# SipNPuff.net
KiCad netlist of a schematic drawn in EAGLE
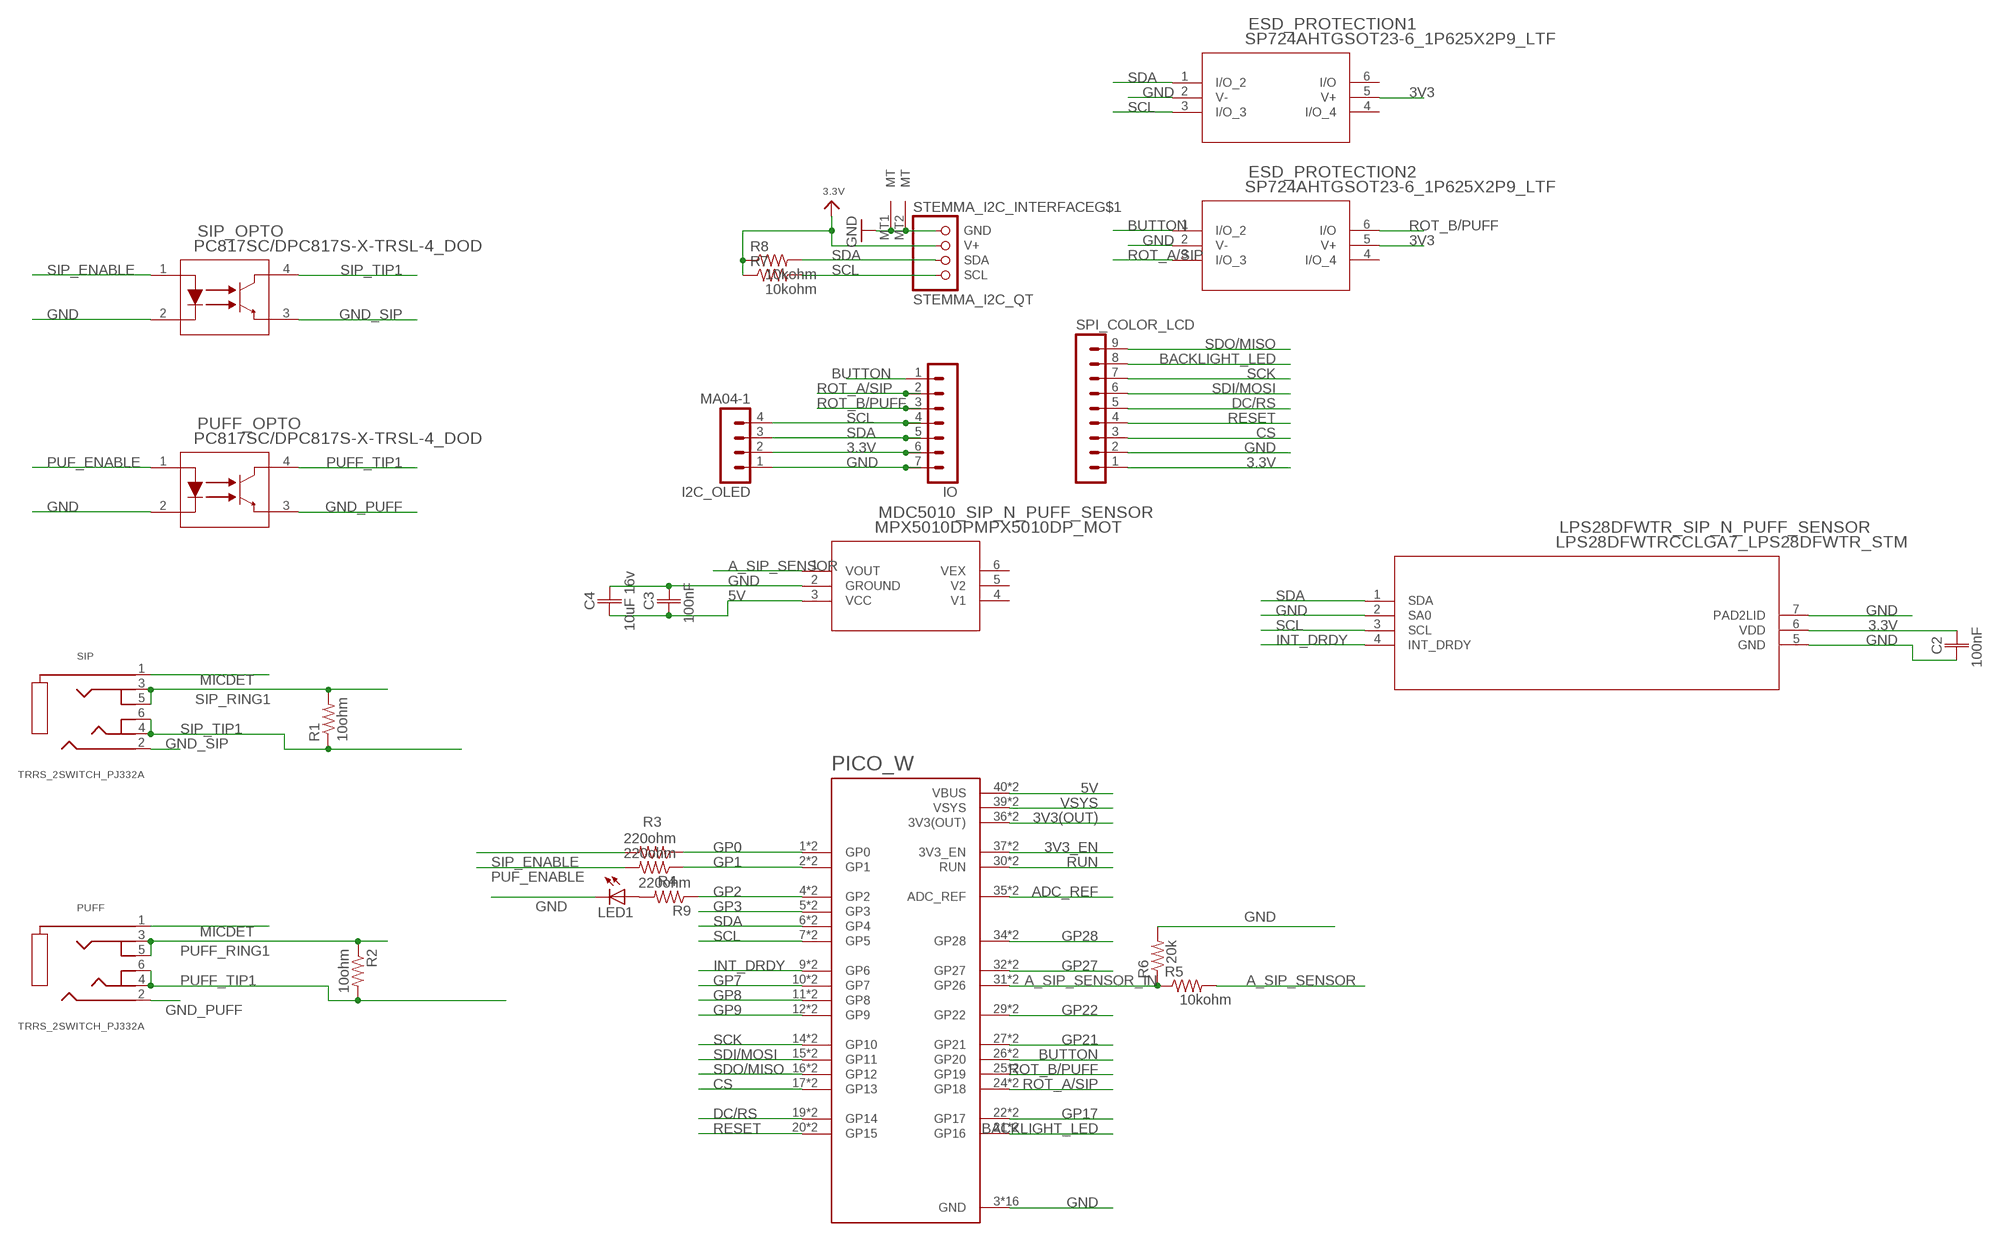
[diagram p0: schematic, sheet 1]

(export (version "E")
  (design (tool "Eeschema 10.0.6"))
  (components
    (comp (ref "C2")
      (value "100nF")
      (footprint "eagle-import:CAPC2012X110")
      (libsource (lib "eagle-import") (part "CCHIP-0805(2012-METRIC)_"))
    )
    (comp (ref "C3")
      (value "100nF")
      (footprint "eagle-import:CAPC2012X110")
      (libsource (lib "eagle-import") (part "CCHIP-0805(2012-METRIC)_"))
    )
    (comp (ref "C4")
      (value "10uF 16v")
      (footprint "eagle-import:CAPC2012X110")
      (libsource (lib "eagle-import") (part "CCHIP-0805(2012-METRIC)_"))
    )
    (comp (ref "ESD_PROTECTION1")
      (value "SP724AHTGSOT23-6_1P625X2P9_LTF")
      (footprint "eagle-import:SOT23-6_1P625X2P9_LTF")
      (fields
        (field (name "MANUFACTURER_PART_NUMBER") "SP724AHTG")
        (field (name "COPYRIGHT") "Copyright (C) 2022 Ultra Librarian. All rights reserved.")
      )
      (libsource (lib "eagle-import") (part "SP724AHTGSOT23-6_1P625X2P9_LTF"))
    )
    (comp (ref "ESD_PROTECTION2")
      (value "SP724AHTGSOT23-6_1P625X2P9_LTF")
      (footprint "eagle-import:SOT23-6_1P625X2P9_LTF")
      (fields
        (field (name "MANUFACTURER_PART_NUMBER") "SP724AHTG")
        (field (name "COPYRIGHT") "Copyright (C) 2022 Ultra Librarian. All rights reserved.")
      )
      (libsource (lib "eagle-import") (part "SP724AHTGSOT23-6_1P625X2P9_LTF"))
    )
    (comp (ref "I2C_OLED")
      (value "MA04-1")
      (footprint "eagle-import:MA04-1")
      (libsource (lib "eagle-import") (part "MA04-1"))
    )
    (comp (ref "IO")
      (value "MA07-1")
      (footprint "eagle-import:MA07-1")
      (libsource (lib "eagle-import") (part "MA07-1"))
    )
    (comp (ref "LED1")
      (value "LEDCHIP-LED0805")
      (footprint "eagle-import:CHIP-LED0805")
      (libsource (lib "eagle-import") (part "LEDCHIP-LED0805"))
    )
    (comp (ref "LPS28DFWTR_SIP_N_PUFF_SENSOR")
      (value "LPS28DFWTRCCLGA7_LPS28DFWTR_STM")
      (footprint "eagle-import:CCLGA7_LPS28DFWTR_STM")
      (fields
        (field (name "MANUFACTURER_PART_NUMBER") "LPS28DFWTR")
        (field (name "COPYRIGHT") "Copyright (C) 2026 Ultra Librarian. All rights reserved.")
      )
      (libsource (lib "eagle-import") (part "LPS28DFWTRCCLGA7_LPS28DFWTR_STM"))
    )
    (comp (ref "MDC5010_SIP_N_PUFF_SENSOR")
      (value "MPX5010DPMPX5010DP_MOT")
      (footprint "eagle-import:MPX5010DP_MOT")
      (fields
        (field (name "MANUFACTURER_PART_NUMBER") "MPX5010DP")
        (field (name "COPYRIGHT") "Copyright (C) 2026 Ultra Librarian. All rights reserved.")
      )
      (libsource (lib "eagle-import") (part "MPX5010DPMPX5010DP_MOT"))
    )
    (comp (ref "PICO_W")
      (value "RASPBERRY_PICO-NO_DEBUG")
      (footprint "eagle-import:PICO-PKG-NO_DEBUG")
      (libsource (lib "eagle-import") (part "RASPBERRY_PICO-NO_DEBUG"))
    )
    (comp (ref "PUFF")
      (value "TRRS_2SWITCH_PJ332A")
      (footprint "eagle-import:PJ-332A")
      (libsource (lib "eagle-import") (part "TRRS_2SWITCH_PJ332A"))
    )
    (comp (ref "PUFF_OPTO")
      (value "PC817SC/DPC817S-X-TRSL-4_DOD")
      (footprint "eagle-import:SL-4_DOD")
      (fields
        (field (name "MANUFACTURER_PART_NUMBER") "DPC817S-X-TR")
        (field (name "COPYRIGHT") "Copyright (C) 2026 Ultra Librarian. All rights reserved.")
      )
      (libsource (lib "eagle-import") (part "DPC817S-X-TRSL-4_DOD"))
    )
    (comp (ref "R1")
      (value "10ohm")
      (footprint "eagle-import:R0805")
      (libsource (lib "eagle-import") (part "R-US_R0805"))
    )
    (comp (ref "R2")
      (value "10ohm")
      (footprint "eagle-import:R0805")
      (libsource (lib "eagle-import") (part "R-US_R0805"))
    )
    (comp (ref "R3")
      (value "220ohm")
      (footprint "eagle-import:R0805")
      (libsource (lib "eagle-import") (part "R-US_R0805"))
    )
    (comp (ref "R4")
      (value "220ohm")
      (footprint "eagle-import:R0805")
      (libsource (lib "eagle-import") (part "R-US_R0805"))
    )
    (comp (ref "R5")
      (value "10kohm")
      (footprint "eagle-import:R0805")
      (libsource (lib "eagle-import") (part "R-US_R0805"))
    )
    (comp (ref "R6")
      (value "20k")
      (footprint "eagle-import:R0805")
      (libsource (lib "eagle-import") (part "R-US_R0805"))
    )
    (comp (ref "R7")
      (value "10kohm")
      (footprint "eagle-import:R0805")
      (libsource (lib "eagle-import") (part "R-US_R0805"))
    )
    (comp (ref "R8")
      (value "10kohm")
      (footprint "eagle-import:R0805")
      (libsource (lib "eagle-import") (part "R-US_R0805"))
    )
    (comp (ref "R9")
      (value "220ohm")
      (footprint "eagle-import:R0805")
      (libsource (lib "eagle-import") (part "R-US_R0805"))
    )
    (comp (ref "SIP")
      (value "TRRS_2SWITCH_PJ332A")
      (footprint "eagle-import:PJ-332A")
      (libsource (lib "eagle-import") (part "TRRS_2SWITCH_PJ332A"))
    )
    (comp (ref "SIP_OPTO")
      (value "PC817SC/DPC817S-X-TRSL-4_DOD")
      (footprint "eagle-import:SL-4_DOD")
      (fields
        (field (name "MANUFACTURER_PART_NUMBER") "DPC817S-X-TR")
        (field (name "COPYRIGHT") "Copyright (C) 2026 Ultra Librarian. All rights reserved.")
      )
      (libsource (lib "eagle-import") (part "DPC817S-X-TRSL-4_DOD"))
    )
    (comp (ref "SPI_COLOR_LCD")
      (value "MA09-1")
      (footprint "eagle-import:MA09-1")
      (libsource (lib "eagle-import") (part "MA09-1"))
    )
    (comp (ref "STEMMA_I2C_INTERFACE")
      (value "STEMMA_I2C_QT")
      (footprint "eagle-import:JST_SH4")
      (libsource (lib "eagle-import") (part "STEMMA_I2C_QT"))
    )
  )
  (nets
    (net (code "1") (name "/3V3") (class "Default")
      (node (ref "ESD_PROTECTION1") (pin "5") (pinfunction "V+_5") (pintype "power_in"))
      (node (ref "ESD_PROTECTION2") (pin "5") (pinfunction "V+_5") (pintype "power_in"))
    )
    (net (code "2") (name "/3V3(OUT)") (class "Default")
      (node (ref "PICO_W") (pin "36") (pinfunction "3V3(OUT)_36") (pintype "power_in"))
      (node (ref "PICO_W") (pin "P$36") (pinfunction "3V3(OUT)_P$36") (pintype "power_in"))
    )
    (net (code "3") (name "/3V3_EN") (class "Default")
      (node (ref "PICO_W") (pin "37") (pinfunction "3V3_EN_37") (pintype "input"))
      (node (ref "PICO_W") (pin "P$37") (pinfunction "3V3_EN_P$37") (pintype "input"))
    )
    (net (code "4") (name "/5V") (class "Default")
      (node (ref "C3") (pin "1") (pinfunction "1_1") (pintype "passive"))
      (node (ref "C4") (pin "1") (pinfunction "1_1") (pintype "passive"))
      (node (ref "MDC5010_SIP_N_PUFF_SENSOR") (pin "3") (pinfunction "VCC_3") (pintype "power_in"))
      (node (ref "PICO_W") (pin "40") (pinfunction "VBUS_40") (pintype "power_in"))
      (node (ref "PICO_W") (pin "P$40") (pinfunction "VBUS_P$40") (pintype "power_in"))
    )
    (net (code "5") (name "/ADC_REF") (class "Default")
      (node (ref "PICO_W") (pin "35") (pinfunction "ADC_REF_35") (pintype "input"))
      (node (ref "PICO_W") (pin "P$35") (pinfunction "ADC_REF_P$35") (pintype "input"))
    )
    (net (code "6") (name "/A_SIP_SENSOR") (class "Default")
      (node (ref "MDC5010_SIP_N_PUFF_SENSOR") (pin "1") (pinfunction "VOUT_1") (pintype "output"))
      (node (ref "R5") (pin "2") (pinfunction "2_2") (pintype "passive"))
    )
    (net (code "7") (name "/A_SIP_SENSOR_IN") (class "Default")
      (node (ref "PICO_W") (pin "31") (pinfunction "GP26_31") (pintype "bidirectional"))
      (node (ref "PICO_W") (pin "P$31") (pinfunction "GP26_P$31") (pintype "bidirectional"))
      (node (ref "R5") (pin "1") (pinfunction "1_1") (pintype "passive"))
      (node (ref "R6") (pin "1") (pinfunction "1_1") (pintype "passive"))
    )
    (net (code "8") (name "/BACKLIGHT_LED") (class "Default")
      (node (ref "PICO_W") (pin "21") (pinfunction "GP16_21") (pintype "bidirectional"))
      (node (ref "PICO_W") (pin "P$21") (pinfunction "GP16_P$21") (pintype "bidirectional"))
      (node (ref "SPI_COLOR_LCD") (pin "8") (pinfunction "8_8") (pintype "passive"))
    )
    (net (code "9") (name "/BUTTON") (class "Default")
      (node (ref "ESD_PROTECTION2") (pin "1") (pinfunction "I/O_2_1") (pintype "passive"))
      (node (ref "IO") (pin "1") (pinfunction "1_1") (pintype "passive"))
      (node (ref "PICO_W") (pin "26") (pinfunction "GP20_26") (pintype "bidirectional"))
      (node (ref "PICO_W") (pin "P$26") (pinfunction "GP20_P$26") (pintype "bidirectional"))
    )
    (net (code "10") (name "/CS") (class "Default")
      (node (ref "PICO_W") (pin "17") (pinfunction "GP13_17") (pintype "bidirectional"))
      (node (ref "PICO_W") (pin "P$17") (pinfunction "GP13_P$17") (pintype "bidirectional"))
      (node (ref "SPI_COLOR_LCD") (pin "3") (pinfunction "3_3") (pintype "passive"))
    )
    (net (code "11") (name "/DC{slash}RS") (class "Default")
      (node (ref "PICO_W") (pin "19") (pinfunction "GP14_19") (pintype "bidirectional"))
      (node (ref "PICO_W") (pin "P$19") (pinfunction "GP14_P$19") (pintype "bidirectional"))
      (node (ref "SPI_COLOR_LCD") (pin "5") (pinfunction "5_5") (pintype "passive"))
    )
    (net (code "12") (name "/GND_PUFF") (class "Default")
      (node (ref "PUFF") (pin "2") (pinfunction "RING1_2") (pintype "passive"))
      (node (ref "PUFF_OPTO") (pin "3") (pinfunction "EMITTER_3") (pintype "passive"))
    )
    (net (code "13") (name "/GND_SIP") (class "Default")
      (node (ref "SIP") (pin "2") (pinfunction "RING1_2") (pintype "passive"))
      (node (ref "SIP_OPTO") (pin "3") (pinfunction "EMITTER_3") (pintype "passive"))
    )
    (net (code "14") (name "/GP0") (class "Default")
      (node (ref "PICO_W") (pin "1") (pinfunction "GP0_1") (pintype "bidirectional"))
      (node (ref "PICO_W") (pin "P$1") (pinfunction "GP0_P$1") (pintype "bidirectional"))
      (node (ref "R3") (pin "1") (pinfunction "1_1") (pintype "passive"))
    )
    (net (code "15") (name "/GP1") (class "Default")
      (node (ref "PICO_W") (pin "2") (pinfunction "GP1_2") (pintype "bidirectional"))
      (node (ref "PICO_W") (pin "P$2") (pinfunction "GP1_P$2") (pintype "bidirectional"))
      (node (ref "R4") (pin "1") (pinfunction "1_1") (pintype "passive"))
    )
    (net (code "16") (name "/GP2") (class "Default")
      (node (ref "PICO_W") (pin "4") (pinfunction "GP2_4") (pintype "bidirectional"))
      (node (ref "PICO_W") (pin "P$4") (pinfunction "GP2_P$4") (pintype "bidirectional"))
      (node (ref "R9") (pin "1") (pinfunction "1_1") (pintype "passive"))
    )
    (net (code "17") (name "/GP3") (class "Default")
      (node (ref "PICO_W") (pin "5") (pinfunction "GP3_5") (pintype "bidirectional"))
      (node (ref "PICO_W") (pin "P$5") (pinfunction "GP3_P$5") (pintype "bidirectional"))
    )
    (net (code "18") (name "/GP7") (class "Default")
      (node (ref "PICO_W") (pin "10") (pinfunction "GP7_10") (pintype "bidirectional"))
      (node (ref "PICO_W") (pin "P$10") (pinfunction "GP7_P$10") (pintype "bidirectional"))
    )
    (net (code "19") (name "/GP8") (class "Default")
      (node (ref "PICO_W") (pin "11") (pinfunction "GP8_11") (pintype "bidirectional"))
      (node (ref "PICO_W") (pin "P$11") (pinfunction "GP8_P$11") (pintype "bidirectional"))
    )
    (net (code "20") (name "/GP9") (class "Default")
      (node (ref "PICO_W") (pin "12") (pinfunction "GP9_12") (pintype "bidirectional"))
      (node (ref "PICO_W") (pin "P$12") (pinfunction "GP9_P$12") (pintype "bidirectional"))
    )
    (net (code "21") (name "/GP17") (class "Default")
      (node (ref "PICO_W") (pin "22") (pinfunction "GP17_22") (pintype "bidirectional"))
      (node (ref "PICO_W") (pin "P$22") (pinfunction "GP17_P$22") (pintype "bidirectional"))
    )
    (net (code "22") (name "/GP21") (class "Default")
      (node (ref "PICO_W") (pin "27") (pinfunction "GP21_27") (pintype "bidirectional"))
      (node (ref "PICO_W") (pin "P$27") (pinfunction "GP21_P$27") (pintype "bidirectional"))
    )
    (net (code "23") (name "/GP22") (class "Default")
      (node (ref "PICO_W") (pin "29") (pinfunction "GP22_29") (pintype "bidirectional"))
      (node (ref "PICO_W") (pin "P$29") (pinfunction "GP22_P$29") (pintype "bidirectional"))
    )
    (net (code "24") (name "/GP27") (class "Default")
      (node (ref "PICO_W") (pin "32") (pinfunction "GP27_32") (pintype "bidirectional"))
      (node (ref "PICO_W") (pin "P$32") (pinfunction "GP27_P$32") (pintype "bidirectional"))
    )
    (net (code "25") (name "/GP28") (class "Default")
      (node (ref "PICO_W") (pin "34") (pinfunction "GP28_34") (pintype "bidirectional"))
      (node (ref "PICO_W") (pin "P$34") (pinfunction "GP28_P$34") (pintype "bidirectional"))
    )
    (net (code "26") (name "/INT_DRDY") (class "Default")
      (node (ref "LPS28DFWTR_SIP_N_PUFF_SENSOR") (pin "4") (pinfunction "INT_DRDY_4") (pintype "input"))
      (node (ref "PICO_W") (pin "9") (pinfunction "GP6_9") (pintype "bidirectional"))
      (node (ref "PICO_W") (pin "P$9") (pinfunction "GP6_P$9") (pintype "bidirectional"))
    )
    (net (code "27") (name "/MICDET") (class "Default")
      (node (ref "PUFF") (pin "1") (pinfunction "RING_1") (pintype "passive"))
      (node (ref "SIP") (pin "1") (pinfunction "RING_1") (pintype "passive"))
    )
    (net (code "28") (name "/PUFF_RING1") (class "Default")
      (node (ref "PUFF") (pin "3") (pinfunction "RING2_3") (pintype "passive"))
      (node (ref "PUFF") (pin "5") (pinfunction "R2_SW_5") (pintype "passive"))
      (node (ref "R2") (pin "1") (pinfunction "1_1") (pintype "passive"))
    )
    (net (code "29") (name "/PUFF_TIP1") (class "Default")
      (node (ref "PUFF") (pin "4") (pinfunction "TIP_4") (pintype "passive"))
      (node (ref "PUFF") (pin "6") (pinfunction "TIP_SW_6") (pintype "passive"))
      (node (ref "PUFF_OPTO") (pin "4") (pinfunction "COLLECTOR_4") (pintype "passive"))
      (node (ref "R2") (pin "2") (pinfunction "2_2") (pintype "passive"))
    )
    (net (code "30") (name "/PUF_ENABLE") (class "Default")
      (node (ref "PUFF_OPTO") (pin "1") (pinfunction "ANODE_1") (pintype "passive"))
      (node (ref "R4") (pin "2") (pinfunction "2_2") (pintype "passive"))
    )
    (net (code "31") (name "/RESET") (class "Default")
      (node (ref "PICO_W") (pin "20") (pinfunction "GP15_20") (pintype "bidirectional"))
      (node (ref "PICO_W") (pin "P$20") (pinfunction "GP15_P$20") (pintype "bidirectional"))
      (node (ref "SPI_COLOR_LCD") (pin "4") (pinfunction "4_4") (pintype "passive"))
    )
    (net (code "32") (name "/ROT_A{slash}SIP") (class "Default")
      (node (ref "ESD_PROTECTION2") (pin "3") (pinfunction "I/O_3_3") (pintype "passive"))
      (node (ref "IO") (pin "2") (pinfunction "2_2") (pintype "passive"))
      (node (ref "PICO_W") (pin "24") (pinfunction "GP18_24") (pintype "bidirectional"))
      (node (ref "PICO_W") (pin "P$24") (pinfunction "GP18_P$24") (pintype "bidirectional"))
    )
    (net (code "33") (name "/ROT_B{slash}PUFF") (class "Default")
      (node (ref "ESD_PROTECTION2") (pin "6") (pinfunction "I/O_6") (pintype "passive"))
      (node (ref "IO") (pin "3") (pinfunction "3_3") (pintype "passive"))
      (node (ref "PICO_W") (pin "25") (pinfunction "GP19_25") (pintype "bidirectional"))
      (node (ref "PICO_W") (pin "P$25") (pinfunction "GP19_P$25") (pintype "bidirectional"))
    )
    (net (code "34") (name "/RUN") (class "Default")
      (node (ref "PICO_W") (pin "30") (pinfunction "RUN_30") (pintype "input"))
      (node (ref "PICO_W") (pin "P$30") (pinfunction "RUN_P$30") (pintype "input"))
    )
    (net (code "35") (name "/SCK") (class "Default")
      (node (ref "PICO_W") (pin "14") (pinfunction "GP10_14") (pintype "bidirectional"))
      (node (ref "PICO_W") (pin "P$14") (pinfunction "GP10_P$14") (pintype "bidirectional"))
      (node (ref "SPI_COLOR_LCD") (pin "7") (pinfunction "7_7") (pintype "passive"))
    )
    (net (code "36") (name "/SCL") (class "Default")
      (node (ref "ESD_PROTECTION1") (pin "3") (pinfunction "I/O_3_3") (pintype "passive"))
      (node (ref "I2C_OLED") (pin "4") (pinfunction "D_4") (pintype "passive"))
      (node (ref "IO") (pin "4") (pinfunction "4_4") (pintype "passive"))
      (node (ref "LPS28DFWTR_SIP_N_PUFF_SENSOR") (pin "3") (pinfunction "SCL_3") (pintype "bidirectional"))
      (node (ref "PICO_W") (pin "7") (pinfunction "GP5_7") (pintype "bidirectional"))
      (node (ref "PICO_W") (pin "P$7") (pinfunction "GP5_P$7") (pintype "bidirectional"))
      (node (ref "R7") (pin "2") (pinfunction "2_2") (pintype "passive"))
      (node (ref "STEMMA_I2C_INTERFACE") (pin "4") (pinfunction "SCL_4") (pintype "passive"))
    )
    (net (code "37") (name "/SDA") (class "Default")
      (node (ref "ESD_PROTECTION1") (pin "1") (pinfunction "I/O_2_1") (pintype "passive"))
      (node (ref "I2C_OLED") (pin "3") (pinfunction "C_3") (pintype "passive"))
      (node (ref "IO") (pin "5") (pinfunction "5_5") (pintype "passive"))
      (node (ref "LPS28DFWTR_SIP_N_PUFF_SENSOR") (pin "1") (pinfunction "SDA_1") (pintype "bidirectional"))
      (node (ref "PICO_W") (pin "6") (pinfunction "GP4_6") (pintype "bidirectional"))
      (node (ref "PICO_W") (pin "P$6") (pinfunction "GP4_P$6") (pintype "bidirectional"))
      (node (ref "R8") (pin "2") (pinfunction "2_2") (pintype "passive"))
      (node (ref "STEMMA_I2C_INTERFACE") (pin "3") (pinfunction "SDA_3") (pintype "passive"))
    )
    (net (code "38") (name "/SDI{slash}MOSI") (class "Default")
      (node (ref "PICO_W") (pin "15") (pinfunction "GP11_15") (pintype "bidirectional"))
      (node (ref "PICO_W") (pin "P$15") (pinfunction "GP11_P$15") (pintype "bidirectional"))
      (node (ref "SPI_COLOR_LCD") (pin "6") (pinfunction "6_6") (pintype "passive"))
    )
    (net (code "39") (name "/SDO{slash}MISO") (class "Default")
      (node (ref "PICO_W") (pin "16") (pinfunction "GP12_16") (pintype "bidirectional"))
      (node (ref "PICO_W") (pin "P$16") (pinfunction "GP12_P$16") (pintype "bidirectional"))
      (node (ref "SPI_COLOR_LCD") (pin "9") (pinfunction "9_9") (pintype "passive"))
    )
    (net (code "40") (name "/SIP_ENABLE") (class "Default")
      (node (ref "R3") (pin "2") (pinfunction "2_2") (pintype "passive"))
      (node (ref "SIP_OPTO") (pin "1") (pinfunction "ANODE_1") (pintype "passive"))
    )
    (net (code "41") (name "/SIP_RING1") (class "Default")
      (node (ref "R1") (pin "2") (pinfunction "2_2") (pintype "passive"))
      (node (ref "SIP") (pin "3") (pinfunction "RING2_3") (pintype "passive"))
      (node (ref "SIP") (pin "5") (pinfunction "R2_SW_5") (pintype "passive"))
    )
    (net (code "42") (name "/SIP_TIP1") (class "Default")
      (node (ref "R1") (pin "1") (pinfunction "1_1") (pintype "passive"))
      (node (ref "SIP") (pin "4") (pinfunction "TIP_4") (pintype "passive"))
      (node (ref "SIP") (pin "6") (pinfunction "TIP_SW_6") (pintype "passive"))
      (node (ref "SIP_OPTO") (pin "4") (pinfunction "COLLECTOR_4") (pintype "passive"))
    )
    (net (code "43") (name "/VSYS") (class "Default")
      (node (ref "PICO_W") (pin "39") (pinfunction "VSYS_39") (pintype "power_in"))
      (node (ref "PICO_W") (pin "P$39") (pinfunction "VSYS_P$39") (pintype "power_in"))
    )
    (net (code "44") (name "3.3V") (class "Default")
      (node (ref "C2") (pin "2") (pinfunction "2_2") (pintype "passive"))
      (node (ref "I2C_OLED") (pin "2") (pinfunction "B_2") (pintype "passive"))
      (node (ref "IO") (pin "6") (pinfunction "6_6") (pintype "passive"))
      (node (ref "LPS28DFWTR_SIP_N_PUFF_SENSOR") (pin "6") (pinfunction "VDD_6") (pintype "power_in"))
      (node (ref "R7") (pin "1") (pinfunction "1_1") (pintype "passive"))
      (node (ref "R8") (pin "1") (pinfunction "1_1") (pintype "passive"))
      (node (ref "SPI_COLOR_LCD") (pin "1") (pinfunction "1_1") (pintype "passive"))
      (node (ref "STEMMA_I2C_INTERFACE") (pin "2") (pinfunction "V+_2") (pintype "passive"))
    )
    (net (code "45") (name "GND") (class "Default")
      (node (ref "C2") (pin "1") (pinfunction "1_1") (pintype "passive"))
      (node (ref "C3") (pin "2") (pinfunction "2_2") (pintype "passive"))
      (node (ref "C4") (pin "2") (pinfunction "2_2") (pintype "passive"))
      (node (ref "ESD_PROTECTION1") (pin "2") (pinfunction "V-_2") (pintype "power_in"))
      (node (ref "ESD_PROTECTION2") (pin "2") (pinfunction "V-_2") (pintype "power_in"))
      (node (ref "I2C_OLED") (pin "1") (pinfunction "A_1") (pintype "passive"))
      (node (ref "IO") (pin "7") (pinfunction "7_7") (pintype "passive"))
      (node (ref "LED1") (pin "C") (pinfunction "C_C") (pintype "passive"))
      (node (ref "LPS28DFWTR_SIP_N_PUFF_SENSOR") (pin "2") (pinfunction "SA0_2") (pintype "bidirectional"))
      (node (ref "LPS28DFWTR_SIP_N_PUFF_SENSOR") (pin "5") (pinfunction "GND_5") (pintype "passive"))
      (node (ref "LPS28DFWTR_SIP_N_PUFF_SENSOR") (pin "7") (pinfunction "PAD2LID_7") (pintype "bidirectional"))
      (node (ref "MDC5010_SIP_N_PUFF_SENSOR") (pin "2") (pinfunction "GROUND_2") (pintype "passive"))
      (node (ref "PICO_W") (pin "13") (pinfunction "GND_13") (pintype "power_in"))
      (node (ref "PICO_W") (pin "18") (pinfunction "GND_18") (pintype "power_in"))
      (node (ref "PICO_W") (pin "23") (pinfunction "GND_23") (pintype "power_in"))
      (node (ref "PICO_W") (pin "28") (pinfunction "GND_28") (pintype "power_in"))
      (node (ref "PICO_W") (pin "3") (pinfunction "GND_3") (pintype "power_in"))
      (node (ref "PICO_W") (pin "33") (pinfunction "GND_33") (pintype "power_in"))
      (node (ref "PICO_W") (pin "38") (pinfunction "GND_38") (pintype "power_in"))
      (node (ref "PICO_W") (pin "8") (pinfunction "GND_8") (pintype "power_in"))
      (node (ref "PICO_W") (pin "P$13") (pinfunction "GND_P$13") (pintype "power_in"))
      (node (ref "PICO_W") (pin "P$18") (pinfunction "GND_P$18") (pintype "power_in"))
      (node (ref "PICO_W") (pin "P$23") (pinfunction "GND_P$23") (pintype "power_in"))
      (node (ref "PICO_W") (pin "P$28") (pinfunction "GND_P$28") (pintype "power_in"))
      (node (ref "PICO_W") (pin "P$3") (pinfunction "GND_P$3") (pintype "power_in"))
      (node (ref "PICO_W") (pin "P$33") (pinfunction "GND_P$33") (pintype "power_in"))
      (node (ref "PICO_W") (pin "P$38") (pinfunction "GND_P$38") (pintype "power_in"))
      (node (ref "PICO_W") (pin "P$8") (pinfunction "GND_P$8") (pintype "power_in"))
      (node (ref "PUFF_OPTO") (pin "2") (pinfunction "CATHODE_2") (pintype "passive"))
      (node (ref "R6") (pin "2") (pinfunction "2_2") (pintype "passive"))
      (node (ref "SIP_OPTO") (pin "2") (pinfunction "CATHODE_2") (pintype "passive"))
      (node (ref "SPI_COLOR_LCD") (pin "2") (pinfunction "2_2") (pintype "passive"))
      (node (ref "STEMMA_I2C_INTERFACE") (pin "1") (pinfunction "GND_1") (pintype "passive"))
      (node (ref "STEMMA_I2C_INTERFACE") (pin "MT1") (pinfunction "MT_MT1") (pintype "bidirectional"))
      (node (ref "STEMMA_I2C_INTERFACE") (pin "MT2") (pinfunction "MT_MT2") (pintype "bidirectional"))
    )
    (net (code "46") (name "Net-(LED1-PadA)") (class "Default")
      (node (ref "LED1") (pin "A") (pinfunction "A_A") (pintype "passive"))
      (node (ref "R9") (pin "2") (pinfunction "2_2") (pintype "passive"))
    )
    (net (code "47") (name "unconnected-(ESD_PROTECTION1-I{slash}O-Pad6)") (class "Default")
      (node (ref "ESD_PROTECTION1") (pin "6") (pinfunction "I/O_6") (pintype "passive"))
    )
    (net (code "48") (name "unconnected-(ESD_PROTECTION1-I{slash}O_4-Pad4)") (class "Default")
      (node (ref "ESD_PROTECTION1") (pin "4") (pinfunction "I/O_4_4") (pintype "passive"))
    )
    (net (code "49") (name "unconnected-(ESD_PROTECTION2-I{slash}O_4-Pad4)") (class "Default")
      (node (ref "ESD_PROTECTION2") (pin "4") (pinfunction "I/O_4_4") (pintype "passive"))
    )
    (net (code "50") (name "unconnected-(MDC5010_SIP_N_PUFF_SENSOR-V1-Pad4)") (class "Default")
      (node (ref "MDC5010_SIP_N_PUFF_SENSOR") (pin "4") (pinfunction "V1_4") (pintype "bidirectional"))
    )
    (net (code "51") (name "unconnected-(MDC5010_SIP_N_PUFF_SENSOR-V2-Pad5)") (class "Default")
      (node (ref "MDC5010_SIP_N_PUFF_SENSOR") (pin "5") (pinfunction "V2_5") (pintype "bidirectional"))
    )
    (net (code "52") (name "unconnected-(MDC5010_SIP_N_PUFF_SENSOR-VEX-Pad6)") (class "Default")
      (node (ref "MDC5010_SIP_N_PUFF_SENSOR") (pin "6") (pinfunction "VEX_6") (pintype "passive"))
    )
  )
)
